# RFID.net
KiCad netlist of a schematic drawn in Altium Designer
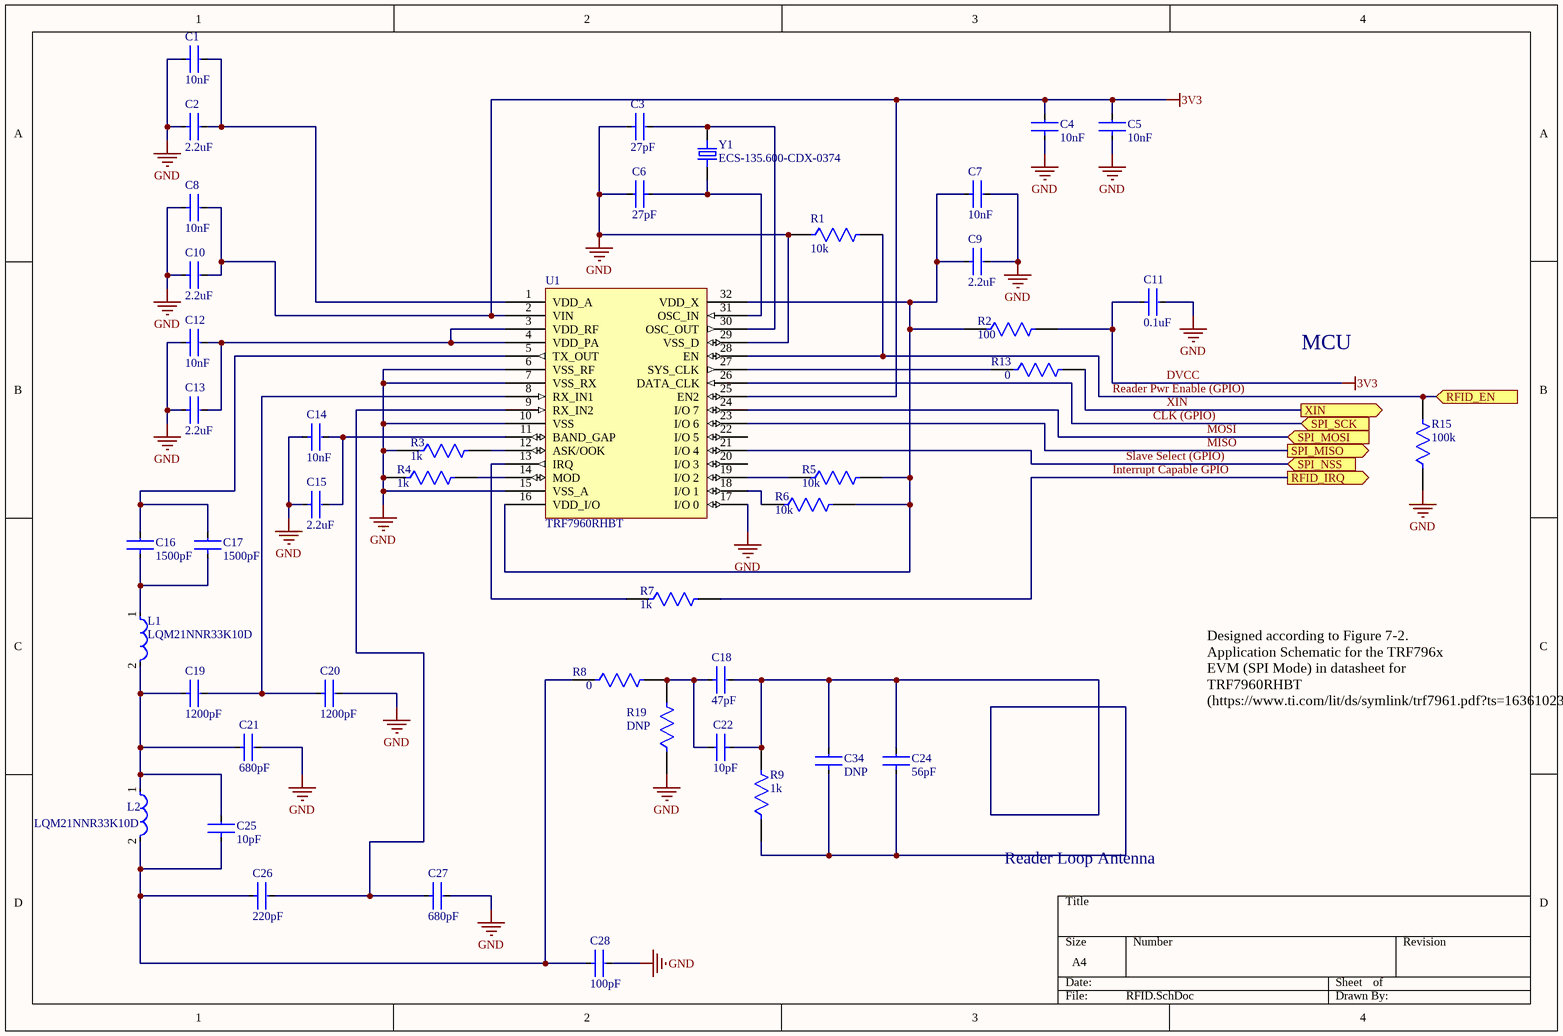
[diagram p0: RFID.SchDoc]

(export (version "E")
  (design (tool "Eeschema 10.0.6"))
  (components
    (comp (ref "C1")
      (value "10nF")
      (footprint "FP-GCJ21B-0_3-IPC_A")
      (description "Multilayer Ceramic Capacitors MLCC - SMD/SMT 0805 2.2uF 10%, 16VDC,  X7R 15%")
      (fields (field (name "TOLERANCE") "10%"))
      (libsource (lib "Altium Content Vault") (part "02cd4be3c70576c341d710602a673aa"))
    )
    (comp (ref "C2")
      (value "2.2uF")
      (footprint "FP-GCJ21B-0_3-IPC_A")
      (description "Multilayer Ceramic Capacitors MLCC - SMD/SMT 0805 2.2uF 10%, 16VDC,  X7R 15%")
      (fields (field (name "TOLERANCE") "10%"))
      (libsource (lib "Altium Content Vault") (part "02cd4be3c70576c341d710602a673aa"))
    )
    (comp (ref "C3")
      (value "27pF")
      (footprint "FP-GCJ21B-0_3-IPC_A")
      (description "Multilayer Ceramic Capacitors MLCC - SMD/SMT 0805 2.2uF 10%, 16VDC,  X7R 15%")
      (fields (field (name "TOLERANCE") "10%"))
      (libsource (lib "Altium Content Vault") (part "02cd4be3c70576c341d710602a673aa"))
    )
    (comp (ref "C4")
      (value "10nF")
      (footprint "FP-GCJ21B-0_3-IPC_A")
      (description "Multilayer Ceramic Capacitors MLCC - SMD/SMT 0805 2.2uF 10%, 16VDC,  X7R 15%")
      (fields (field (name "TOLERANCE") "10%"))
      (libsource (lib "Altium Content Vault") (part "02cd4be3c70576c341d710602a673aa"))
    )
    (comp (ref "C5")
      (value "10nF")
      (footprint "FP-GCJ21B-0_3-IPC_A")
      (description "Multilayer Ceramic Capacitors MLCC - SMD/SMT 0805 2.2uF 10%, 16VDC,  X7R 15%")
      (fields (field (name "TOLERANCE") "10%"))
      (libsource (lib "Altium Content Vault") (part "02cd4be3c70576c341d710602a673aa"))
    )
    (comp (ref "C6")
      (value "27pF")
      (footprint "FP-GCJ21B-0_3-IPC_A")
      (description "Multilayer Ceramic Capacitors MLCC - SMD/SMT 0805 2.2uF 10%, 16VDC,  X7R 15%")
      (fields (field (name "TOLERANCE") "10%"))
      (libsource (lib "Altium Content Vault") (part "02cd4be3c70576c341d710602a673aa"))
    )
    (comp (ref "C7")
      (value "10nF")
      (footprint "FP-GCJ21B-0_3-IPC_A")
      (description "Multilayer Ceramic Capacitors MLCC - SMD/SMT 0805 2.2uF 10%, 16VDC,  X7R 15%")
      (fields (field (name "TOLERANCE") "10%"))
      (libsource (lib "Altium Content Vault") (part "02cd4be3c70576c341d710602a673aa"))
    )
    (comp (ref "C8")
      (value "10nF")
      (footprint "FP-GCJ21B-0_3-IPC_A")
      (description "Multilayer Ceramic Capacitors MLCC - SMD/SMT 0805 2.2uF 10%, 16VDC,  X7R 15%")
      (fields (field (name "TOLERANCE") "10%"))
      (libsource (lib "Altium Content Vault") (part "02cd4be3c70576c341d710602a673aa"))
    )
    (comp (ref "C9")
      (value "2.2uF")
      (footprint "FP-GCJ21B-0_3-IPC_A")
      (description "Multilayer Ceramic Capacitors MLCC - SMD/SMT 0805 2.2uF 10%, 16VDC,  X7R 15%")
      (fields (field (name "TOLERANCE") "10%"))
      (libsource (lib "Altium Content Vault") (part "02cd4be3c70576c341d710602a673aa"))
    )
    (comp (ref "C10")
      (value "2.2uF")
      (footprint "FP-GCJ21B-0_3-IPC_A")
      (description "Multilayer Ceramic Capacitors MLCC - SMD/SMT 0805 2.2uF 10%, 16VDC,  X7R 15%")
      (fields (field (name "TOLERANCE") "10%"))
      (libsource (lib "Altium Content Vault") (part "02cd4be3c70576c341d710602a673aa"))
    )
    (comp (ref "C11")
      (value "0.1uF")
      (footprint "FP-GCJ21B-0_3-IPC_A")
      (description "Multilayer Ceramic Capacitors MLCC - SMD/SMT 0805 2.2uF 10%, 16VDC,  X7R 15%")
      (fields (field (name "TOLERANCE") "10%"))
      (libsource (lib "Altium Content Vault") (part "02cd4be3c70576c341d710602a673aa"))
    )
    (comp (ref "C12")
      (value "10nF")
      (footprint "FP-GCJ21B-0_3-IPC_A")
      (description "Multilayer Ceramic Capacitors MLCC - SMD/SMT 0805 2.2uF 10%, 16VDC,  X7R 15%")
      (fields (field (name "TOLERANCE") "10%"))
      (libsource (lib "Altium Content Vault") (part "02cd4be3c70576c341d710602a673aa"))
    )
    (comp (ref "C13")
      (value "2.2uF")
      (footprint "FP-GCJ21B-0_3-IPC_A")
      (description "Multilayer Ceramic Capacitors MLCC - SMD/SMT 0805 2.2uF 10%, 16VDC,  X7R 15%")
      (fields (field (name "TOLERANCE") "10%"))
      (libsource (lib "Altium Content Vault") (part "02cd4be3c70576c341d710602a673aa"))
    )
    (comp (ref "C14")
      (value "10nF")
      (footprint "FP-GCJ21B-0_3-IPC_A")
      (description "Multilayer Ceramic Capacitors MLCC - SMD/SMT 0805 2.2uF 10%, 16VDC,  X7R 15%")
      (fields (field (name "TOLERANCE") "10%"))
      (libsource (lib "Altium Content Vault") (part "02cd4be3c70576c341d710602a673aa"))
    )
    (comp (ref "C15")
      (value "2.2uF")
      (footprint "FP-GCJ21B-0_3-IPC_A")
      (description "Multilayer Ceramic Capacitors MLCC - SMD/SMT 0805 2.2uF 10%, 16VDC,  X7R 15%")
      (fields (field (name "TOLERANCE") "10%"))
      (libsource (lib "Altium Content Vault") (part "02cd4be3c70576c341d710602a673aa"))
    )
    (comp (ref "C16")
      (value "1500pF")
      (footprint "FP-GCJ21B-0_3-IPC_A")
      (description "Multilayer Ceramic Capacitors MLCC - SMD/SMT 0805 2.2uF 10%, 16VDC,  X7R 15%")
      (fields (field (name "TOLERANCE") "10%"))
      (libsource (lib "Altium Content Vault") (part "02cd4be3c70576c341d710602a673aa"))
    )
    (comp (ref "C17")
      (value "1500pF")
      (footprint "FP-GCJ21B-0_3-IPC_A")
      (description "Multilayer Ceramic Capacitors MLCC - SMD/SMT 0805 2.2uF 10%, 16VDC,  X7R 15%")
      (fields (field (name "TOLERANCE") "10%"))
      (libsource (lib "Altium Content Vault") (part "02cd4be3c70576c341d710602a673aa"))
    )
    (comp (ref "C18")
      (value "47pF")
      (footprint "FP-GCJ21B-0_3-IPC_A")
      (description "Multilayer Ceramic Capacitors MLCC - SMD/SMT 0805 2.2uF 10%, 16VDC,  X7R 15%")
      (fields (field (name "TOLERANCE") "10%"))
      (libsource (lib "Altium Content Vault") (part "02cd4be3c70576c341d710602a673aa"))
    )
    (comp (ref "C19")
      (value "1200pF")
      (footprint "FP-GCJ21B-0_3-IPC_A")
      (description "Multilayer Ceramic Capacitors MLCC - SMD/SMT 0805 2.2uF 10%, 16VDC,  X7R 15%")
      (fields (field (name "TOLERANCE") "10%"))
      (libsource (lib "Altium Content Vault") (part "02cd4be3c70576c341d710602a673aa"))
    )
    (comp (ref "C20")
      (value "1200pF")
      (footprint "FP-GCJ21B-0_3-IPC_A")
      (description "Multilayer Ceramic Capacitors MLCC - SMD/SMT 0805 2.2uF 10%, 16VDC,  X7R 15%")
      (fields (field (name "TOLERANCE") "10%"))
      (libsource (lib "Altium Content Vault") (part "02cd4be3c70576c341d710602a673aa"))
    )
    (comp (ref "C21")
      (value "680pF")
      (footprint "FP-GCJ21B-0_3-IPC_A")
      (description "Multilayer Ceramic Capacitors MLCC - SMD/SMT 0805 2.2uF 10%, 16VDC,  X7R 15%")
      (fields (field (name "TOLERANCE") "10%"))
      (libsource (lib "Altium Content Vault") (part "02cd4be3c70576c341d710602a673aa"))
    )
    (comp (ref "C22")
      (value "10pF")
      (footprint "FP-GCJ21B-0_3-IPC_A")
      (description "Multilayer Ceramic Capacitors MLCC - SMD/SMT 0805 2.2uF 10%, 16VDC,  X7R 15%")
      (fields (field (name "TOLERANCE") "10%"))
      (libsource (lib "Altium Content Vault") (part "02cd4be3c70576c341d710602a673aa"))
    )
    (comp (ref "C24")
      (value "56pF")
      (footprint "FP-GCJ21B-0_3-IPC_A")
      (description "Multilayer Ceramic Capacitors MLCC - SMD/SMT 0805 2.2uF 10%, 16VDC,  X7R 15%")
      (fields (field (name "TOLERANCE") "10%"))
      (libsource (lib "Altium Content Vault") (part "02cd4be3c70576c341d710602a673aa"))
    )
    (comp (ref "C25")
      (value "10pF")
      (footprint "FP-GCJ21B-0_3-IPC_A")
      (description "Multilayer Ceramic Capacitors MLCC - SMD/SMT 0805 2.2uF 10%, 16VDC,  X7R 15%")
      (fields (field (name "TOLERANCE") "10%"))
      (libsource (lib "Altium Content Vault") (part "02cd4be3c70576c341d710602a673aa"))
    )
    (comp (ref "C26")
      (value "220pF")
      (footprint "FP-GCJ21B-0_3-IPC_A")
      (description "Multilayer Ceramic Capacitors MLCC - SMD/SMT 0805 2.2uF 10%, 16VDC,  X7R 15%")
      (fields (field (name "TOLERANCE") "10%"))
      (libsource (lib "Altium Content Vault") (part "02cd4be3c70576c341d710602a673aa"))
    )
    (comp (ref "C27")
      (value "680pF")
      (footprint "FP-GCJ21B-0_3-IPC_A")
      (description "Multilayer Ceramic Capacitors MLCC - SMD/SMT 0805 2.2uF 10%, 16VDC,  X7R 15%")
      (fields (field (name "TOLERANCE") "10%"))
      (libsource (lib "Altium Content Vault") (part "02cd4be3c70576c341d710602a673aa"))
    )
    (comp (ref "C28")
      (value "100pF")
      (footprint "FP-GCJ21B-0_3-IPC_A")
      (description "Multilayer Ceramic Capacitors MLCC - SMD/SMT 0805 2.2uF 10%, 16VDC,  X7R 15%")
      (fields (field (name "TOLERANCE") "10%"))
      (libsource (lib "Altium Content Vault") (part "02cd4be3c70576c341d710602a673aa"))
    )
    (comp (ref "C34")
      (value "DNP")
      (footprint "FP-GCJ21B-0_3-IPC_A")
      (description "Multilayer Ceramic Capacitors MLCC - SMD/SMT 0805 2.2uF 10%, 16VDC,  X7R 15%")
      (fields (field (name "TOLERANCE") "10%"))
      (libsource (lib "Altium Content Vault") (part "02cd4be3c70576c341d710602a673aa"))
    )
    (comp (ref "L1")
      (value "LQM21NNR33K10D")
      (footprint "FP-LQM21DN_00-IPC_A")
      (description "Multilayer Type Inductor for General Circuits, 0805 (2012), 0.33μH, 10%, 0.48Ω, 250mA")
      (fields (field (name "TOLERANCE") "10%"))
      (libsource (lib "Altium Content Vault") (part "725321dda6339637d4d059423bc1c3c"))
    )
    (comp (ref "L2")
      (value "LQM21NNR33K10D")
      (footprint "FP-LQM21DN_00-IPC_A")
      (description "Multilayer Type Inductor for General Circuits, 0805 (2012), 0.33μH, 10%, 0.48Ω, 250mA")
      (fields (field (name "TOLERANCE") "10%"))
      (libsource (lib "Altium Content Vault") (part "725321dda6339637d4d059423bc1c3c"))
    )
    (comp (ref "R1")
      (value "10k")
      (footprint "FP-AC0603-MFG")
      (description "RES SMD 60.4 OHM 1% 1/10W 0603")
      (fields
        (field (name "MANUFACTURER PART NUMBER") "AC0603FR-0760R4L")
        (field (name "OCTOPART") "https://octopart.com/ac0603fr-0760r4l-yageo-71367350")
      )
      (libsource (lib "Altium Content Vault") (part "1029c3af85768c4190bb7ad29bc67b5"))
    )
    (comp (ref "R2")
      (value "100")
      (footprint "FP-AC0603-MFG")
      (description "RES SMD 60.4 OHM 1% 1/10W 0603")
      (fields
        (field (name "MANUFACTURER PART NUMBER") "AC0603FR-0760R4L")
        (field (name "OCTOPART") "https://octopart.com/ac0603fr-0760r4l-yageo-71367350")
      )
      (libsource (lib "Altium Content Vault") (part "1029c3af85768c4190bb7ad29bc67b5"))
    )
    (comp (ref "R3")
      (value "1k")
      (footprint "FP-AC0603-MFG")
      (description "RES SMD 60.4 OHM 1% 1/10W 0603")
      (fields
        (field (name "MANUFACTURER PART NUMBER") "AC0603FR-0760R4L")
        (field (name "OCTOPART") "https://octopart.com/ac0603fr-0760r4l-yageo-71367350")
      )
      (libsource (lib "Altium Content Vault") (part "1029c3af85768c4190bb7ad29bc67b5"))
    )
    (comp (ref "R4")
      (value "1k")
      (footprint "FP-AC0603-MFG")
      (description "RES SMD 60.4 OHM 1% 1/10W 0603")
      (fields
        (field (name "MANUFACTURER PART NUMBER") "AC0603FR-0760R4L")
        (field (name "OCTOPART") "https://octopart.com/ac0603fr-0760r4l-yageo-71367350")
      )
      (libsource (lib "Altium Content Vault") (part "1029c3af85768c4190bb7ad29bc67b5"))
    )
    (comp (ref "R5")
      (value "10k")
      (footprint "FP-AC0603-MFG")
      (description "RES SMD 60.4 OHM 1% 1/10W 0603")
      (fields
        (field (name "MANUFACTURER PART NUMBER") "AC0603FR-0760R4L")
        (field (name "OCTOPART") "https://octopart.com/ac0603fr-0760r4l-yageo-71367350")
      )
      (libsource (lib "Altium Content Vault") (part "1029c3af85768c4190bb7ad29bc67b5"))
    )
    (comp (ref "R6")
      (value "10k")
      (footprint "FP-AC0603-MFG")
      (description "RES SMD 60.4 OHM 1% 1/10W 0603")
      (fields
        (field (name "MANUFACTURER PART NUMBER") "AC0603FR-0760R4L")
        (field (name "OCTOPART") "https://octopart.com/ac0603fr-0760r4l-yageo-71367350")
      )
      (libsource (lib "Altium Content Vault") (part "1029c3af85768c4190bb7ad29bc67b5"))
    )
    (comp (ref "R7")
      (value "1k")
      (footprint "FP-AC0603-MFG")
      (description "RES SMD 60.4 OHM 1% 1/10W 0603")
      (fields
        (field (name "MANUFACTURER PART NUMBER") "AC0603FR-0760R4L")
        (field (name "OCTOPART") "https://octopart.com/ac0603fr-0760r4l-yageo-71367350")
      )
      (libsource (lib "Altium Content Vault") (part "1029c3af85768c4190bb7ad29bc67b5"))
    )
    (comp (ref "R8")
      (value "0")
      (footprint "FP-AC0603-MFG")
      (description "RES SMD 60.4 OHM 1% 1/10W 0603")
      (fields
        (field (name "MANUFACTURER PART NUMBER") "AC0603FR-0760R4L")
        (field (name "OCTOPART") "https://octopart.com/ac0603fr-0760r4l-yageo-71367350")
      )
      (libsource (lib "Altium Content Vault") (part "1029c3af85768c4190bb7ad29bc67b5"))
    )
    (comp (ref "R9")
      (value "1k")
      (footprint "FP-AC0603-MFG")
      (description "RES SMD 60.4 OHM 1% 1/10W 0603")
      (fields
        (field (name "MANUFACTURER PART NUMBER") "AC0603FR-0760R4L")
        (field (name "OCTOPART") "https://octopart.com/ac0603fr-0760r4l-yageo-71367350")
      )
      (libsource (lib "Altium Content Vault") (part "1029c3af85768c4190bb7ad29bc67b5"))
    )
    (comp (ref "R13")
      (value "0")
      (footprint "FP-AC0603-MFG")
      (description "RES SMD 60.4 OHM 1% 1/10W 0603")
      (fields
        (field (name "MANUFACTURER PART NUMBER") "AC0603FR-0760R4L")
        (field (name "OCTOPART") "https://octopart.com/ac0603fr-0760r4l-yageo-71367350")
      )
      (libsource (lib "Altium Content Vault") (part "1029c3af85768c4190bb7ad29bc67b5"))
    )
    (comp (ref "R15")
      (value "100k")
      (footprint "FP-AC0603-MFG")
      (description "RES SMD 60.4 OHM 1% 1/10W 0603")
      (fields
        (field (name "MANUFACTURER PART NUMBER") "AC0603FR-0760R4L")
        (field (name "OCTOPART") "https://octopart.com/ac0603fr-0760r4l-yageo-71367350")
      )
      (libsource (lib "Altium Content Vault") (part "1029c3af85768c4190bb7ad29bc67b5"))
    )
    (comp (ref "R19")
      (value "DNP")
      (footprint "FP-AC0603-MFG")
      (description "RES SMD 60.4 OHM 1% 1/10W 0603")
      (fields
        (field (name "MANUFACTURER PART NUMBER") "AC0603FR-0760R4L")
        (field (name "OCTOPART") "https://octopart.com/ac0603fr-0760r4l-yageo-71367350")
      )
      (libsource (lib "Altium Content Vault") (part "1029c3af85768c4190bb7ad29bc67b5"))
    )
    (comp (ref "U1")
      (value "TRF7960RHBT")
      (footprint "IC_ADS125H01IRHBT")
      (description "TRF7960 Multi-Protocol Fully Integrated 13.56-MHz RFID Reader/Writer IC 32-VQFN -40 to 110")
      (libsource (lib "Schlib") (part "TRF7960RHBT"))
    )
    (comp (ref "Y1")
      (value "ECS-135.600-CDX-0374")
      (footprint "XTAL_ECS-135.600-CDX-0374")
      (libsource (lib "Schlib") (part "ECS-135.600-CDX-0374"))
    )
  )
  (nets
    (net (code "1") (name "/CLK (GPIO)") (class "Default")
      (node (ref "U1") (pin "26") (pinfunction "DATA_CLK_26") (pintype "input"))
    )
    (net (code "2") (name "/Interrupt Capable GPIO") (class "Default")
      (node (ref "R7") (pin "2") (pinfunction "2_2") (pintype "passive"))
    )
    (net (code "3") (name "/MISO") (class "Default")
      (node (ref "U1") (pin "23") (pinfunction "I/O_6_23") (pintype "bidirectional"))
    )
    (net (code "4") (name "/MOSI") (class "Default")
      (node (ref "U1") (pin "24") (pinfunction "I/O_7_24") (pintype "bidirectional"))
    )
    (net (code "5") (name "/Reader Pwr Enable (GPIO)") (class "Default")
      (node (ref "R1") (pin "2") (pinfunction "2_2") (pintype "passive"))
      (node (ref "R15") (pin "2") (pinfunction "2_2") (pintype "passive"))
      (node (ref "U1") (pin "28") (pinfunction "EN_28") (pintype "bidirectional"))
    )
    (net (code "6") (name "/Slave Select (GPIO)") (class "Default")
      (node (ref "U1") (pin "21") (pinfunction "I/O_4_21") (pintype "bidirectional"))
    )
    (net (code "7") (name "/XIN") (class "Default")
      (node (ref "R13") (pin "2") (pinfunction "2_2") (pintype "passive"))
    )
    (net (code "8") (name "3V3") (class "Default")
      (node (ref "C10") (pin "2") (pinfunction "2_2") (pintype "passive"))
      (node (ref "C11") (pin "1") (pinfunction "1_1") (pintype "passive"))
      (node (ref "C4") (pin "2") (pinfunction "2_2") (pintype "passive"))
      (node (ref "C5") (pin "2") (pinfunction "2_2") (pintype "passive"))
      (node (ref "C8") (pin "2") (pinfunction "2_2") (pintype "passive"))
      (node (ref "R2") (pin "2") (pinfunction "2_2") (pintype "passive"))
      (node (ref "U1") (pin "2") (pinfunction "VIN_2") (pintype "power_in"))
      (node (ref "U1") (pin "25") (pinfunction "EN2_25") (pintype "bidirectional"))
    )
    (net (code "9") (name "GND") (class "Default")
      (node (ref "C1") (pin "1") (pinfunction "1_1") (pintype "passive"))
      (node (ref "C10") (pin "1") (pinfunction "1_1") (pintype "passive"))
      (node (ref "C11") (pin "2") (pinfunction "2_2") (pintype "passive"))
      (node (ref "C12") (pin "1") (pinfunction "1_1") (pintype "passive"))
      (node (ref "C13") (pin "1") (pinfunction "1_1") (pintype "passive"))
      (node (ref "C14") (pin "1") (pinfunction "1_1") (pintype "passive"))
      (node (ref "C15") (pin "1") (pinfunction "1_1") (pintype "passive"))
      (node (ref "C2") (pin "1") (pinfunction "1_1") (pintype "passive"))
      (node (ref "C20") (pin "2") (pinfunction "2_2") (pintype "passive"))
      (node (ref "C21") (pin "2") (pinfunction "2_2") (pintype "passive"))
      (node (ref "C27") (pin "2") (pinfunction "2_2") (pintype "passive"))
      (node (ref "C28") (pin "2") (pinfunction "2_2") (pintype "passive"))
      (node (ref "C3") (pin "1") (pinfunction "1_1") (pintype "passive"))
      (node (ref "C4") (pin "1") (pinfunction "1_1") (pintype "passive"))
      (node (ref "C5") (pin "1") (pinfunction "1_1") (pintype "passive"))
      (node (ref "C6") (pin "2") (pinfunction "2_2") (pintype "passive"))
      (node (ref "C7") (pin "2") (pinfunction "2_2") (pintype "passive"))
      (node (ref "C8") (pin "1") (pinfunction "1_1") (pintype "passive"))
      (node (ref "C9") (pin "2") (pinfunction "2_2") (pintype "passive"))
      (node (ref "R1") (pin "1") (pinfunction "1_1") (pintype "passive"))
      (node (ref "R15") (pin "1") (pinfunction "1_1") (pintype "passive"))
      (node (ref "R19") (pin "1") (pinfunction "1_1") (pintype "passive"))
      (node (ref "R3") (pin "1") (pinfunction "1_1") (pintype "passive"))
      (node (ref "R4") (pin "1") (pinfunction "1_1") (pintype "passive"))
      (node (ref "U1") (pin "10") (pinfunction "VSS_10") (pintype "power_in"))
      (node (ref "U1") (pin "15") (pinfunction "VSS_A_15") (pintype "power_in"))
      (node (ref "U1") (pin "17") (pinfunction "I/O_0_17") (pintype "bidirectional"))
      (node (ref "U1") (pin "29") (pinfunction "VSS_D_29") (pintype "bidirectional"))
      (node (ref "U1") (pin "6") (pinfunction "VSS_RF_6") (pintype "power_in"))
      (node (ref "U1") (pin "7") (pinfunction "VSS_RX_7") (pintype "power_in"))
    )
    (net (code "10") (name "Net-(C16-Pad1)") (class "Default")
      (node (ref "C16") (pin "1") (pinfunction "1_1") (pintype "passive"))
      (node (ref "C17") (pin "1") (pinfunction "1_1") (pintype "passive"))
      (node (ref "L1") (pin "1") (pinfunction "1_1") (pintype "passive"))
    )
    (net (code "11") (name "Net-(C18-Pad1)") (class "Default")
      (node (ref "C18") (pin "1") (pinfunction "1_1") (pintype "passive"))
      (node (ref "C22") (pin "2") (pinfunction "2_2") (pintype "passive"))
      (node (ref "R19") (pin "2") (pinfunction "2_2") (pintype "passive"))
      (node (ref "R8") (pin "2") (pinfunction "2_2") (pintype "passive"))
    )
    (net (code "12") (name "Net-(C18-Pad2)") (class "Default")
      (node (ref "C18") (pin "2") (pinfunction "2_2") (pintype "passive"))
      (node (ref "C22") (pin "1") (pinfunction "1_1") (pintype "passive"))
      (node (ref "C24") (pin "1") (pinfunction "1_1") (pintype "passive"))
      (node (ref "C24") (pin "2") (pinfunction "2_2") (pintype "passive"))
      (node (ref "C34") (pin "1") (pinfunction "1_1") (pintype "passive"))
      (node (ref "C34") (pin "2") (pinfunction "2_2") (pintype "passive"))
      (node (ref "R9") (pin "1") (pinfunction "1_1") (pintype "passive"))
      (node (ref "R9") (pin "2") (pinfunction "2_2") (pintype "passive"))
    )
    (net (code "13") (name "Net-(C19-Pad1)") (class "Default")
      (node (ref "C19") (pin "1") (pinfunction "1_1") (pintype "passive"))
      (node (ref "C21") (pin "1") (pinfunction "1_1") (pintype "passive"))
      (node (ref "C25") (pin "2") (pinfunction "2_2") (pintype "passive"))
      (node (ref "L1") (pin "2") (pinfunction "2_2") (pintype "passive"))
      (node (ref "L2") (pin "1") (pinfunction "1_1") (pintype "passive"))
    )
    (net (code "14") (name "Net-(C25-Pad1)") (class "Default")
      (node (ref "C25") (pin "1") (pinfunction "1_1") (pintype "passive"))
      (node (ref "C26") (pin "1") (pinfunction "1_1") (pintype "passive"))
      (node (ref "C28") (pin "1") (pinfunction "1_1") (pintype "passive"))
      (node (ref "L2") (pin "2") (pinfunction "2_2") (pintype "passive"))
      (node (ref "R8") (pin "1") (pinfunction "1_1") (pintype "passive"))
    )
    (net (code "15") (name "Net-(U1-ASK{slash}OOK)") (class "Default")
      (node (ref "R3") (pin "2") (pinfunction "2_2") (pintype "passive"))
      (node (ref "U1") (pin "12") (pinfunction "ASK/OOK_12") (pintype "bidirectional"))
    )
    (net (code "16") (name "Net-(U1-BAND_GAP)") (class "Default")
      (node (ref "C14") (pin "2") (pinfunction "2_2") (pintype "passive"))
      (node (ref "C15") (pin "2") (pinfunction "2_2") (pintype "passive"))
      (node (ref "U1") (pin "11") (pinfunction "BAND_GAP_11") (pintype "bidirectional"))
    )
    (net (code "17") (name "Net-(U1-IRQ)") (class "Default")
      (node (ref "R7") (pin "1") (pinfunction "1_1") (pintype "passive"))
      (node (ref "U1") (pin "13") (pinfunction "IRQ_13") (pintype "output"))
    )
    (net (code "18") (name "Net-(U1-I{slash}O_1)") (class "Default")
      (node (ref "R6") (pin "1") (pinfunction "1_1") (pintype "passive"))
      (node (ref "U1") (pin "18") (pinfunction "I/O_1_18") (pintype "bidirectional"))
    )
    (net (code "19") (name "Net-(U1-I{slash}O_2)") (class "Default")
      (node (ref "R5") (pin "1") (pinfunction "1_1") (pintype "passive"))
      (node (ref "U1") (pin "19") (pinfunction "I/O_2_19") (pintype "bidirectional"))
    )
    (net (code "20") (name "Net-(U1-MOD)") (class "Default")
      (node (ref "R4") (pin "2") (pinfunction "2_2") (pintype "passive"))
      (node (ref "U1") (pin "14") (pinfunction "MOD_14") (pintype "bidirectional"))
    )
    (net (code "21") (name "Net-(U1-OSC_IN)") (class "Default")
      (node (ref "C6") (pin "1") (pinfunction "1_1") (pintype "passive"))
      (node (ref "U1") (pin "31") (pinfunction "OSC_IN_31") (pintype "input"))
      (node (ref "Y1") (pin "1") (pinfunction "1_1") (pintype "passive"))
    )
    (net (code "22") (name "Net-(U1-OSC_OUT)") (class "Default")
      (node (ref "C3") (pin "2") (pinfunction "2_2") (pintype "passive"))
      (node (ref "U1") (pin "30") (pinfunction "OSC_OUT_30") (pintype "output"))
      (node (ref "Y1") (pin "2") (pinfunction "2_2") (pintype "passive"))
    )
    (net (code "23") (name "Net-(U1-RX_IN1)") (class "Default")
      (node (ref "C19") (pin "2") (pinfunction "2_2") (pintype "passive"))
      (node (ref "C20") (pin "1") (pinfunction "1_1") (pintype "passive"))
      (node (ref "U1") (pin "8") (pinfunction "RX_IN1_8") (pintype "input"))
    )
    (net (code "24") (name "Net-(U1-RX_IN2)") (class "Default")
      (node (ref "C26") (pin "2") (pinfunction "2_2") (pintype "passive"))
      (node (ref "C27") (pin "1") (pinfunction "1_1") (pintype "passive"))
      (node (ref "U1") (pin "9") (pinfunction "RX_IN2_9") (pintype "input"))
    )
    (net (code "25") (name "Net-(U1-SYS_CLK)") (class "Default")
      (node (ref "R13") (pin "1") (pinfunction "1_1") (pintype "passive"))
      (node (ref "U1") (pin "27") (pinfunction "SYS_CLK_27") (pintype "output"))
    )
    (net (code "26") (name "Net-(U1-TX_OUT)") (class "Default")
      (node (ref "C16") (pin "2") (pinfunction "2_2") (pintype "passive"))
      (node (ref "C17") (pin "2") (pinfunction "2_2") (pintype "passive"))
      (node (ref "U1") (pin "5") (pinfunction "TX_OUT_5") (pintype "output"))
    )
    (net (code "27") (name "Net-(U1-VDD_A)") (class "Default")
      (node (ref "C1") (pin "2") (pinfunction "2_2") (pintype "passive"))
      (node (ref "C2") (pin "2") (pinfunction "2_2") (pintype "passive"))
      (node (ref "U1") (pin "1") (pinfunction "VDD_A_1") (pintype "power_in"))
    )
    (net (code "28") (name "Net-(U1-VDD_I{slash}O)") (class "Default")
      (node (ref "C7") (pin "1") (pinfunction "1_1") (pintype "passive"))
      (node (ref "C9") (pin "1") (pinfunction "1_1") (pintype "passive"))
      (node (ref "R2") (pin "1") (pinfunction "1_1") (pintype "passive"))
      (node (ref "R5") (pin "2") (pinfunction "2_2") (pintype "passive"))
      (node (ref "R6") (pin "2") (pinfunction "2_2") (pintype "passive"))
      (node (ref "U1") (pin "16") (pinfunction "VDD_I/O_16") (pintype "power_in"))
      (node (ref "U1") (pin "32") (pinfunction "VDD_X_32") (pintype "power_in"))
    )
    (net (code "29") (name "Net-(U1-VDD_PA)") (class "Default")
      (node (ref "C12") (pin "2") (pinfunction "2_2") (pintype "passive"))
      (node (ref "C13") (pin "2") (pinfunction "2_2") (pintype "passive"))
      (node (ref "U1") (pin "3") (pinfunction "VDD_RF_3") (pintype "power_in"))
      (node (ref "U1") (pin "4") (pinfunction "VDD_PA_4") (pintype "power_in"))
    )
    (net (code "30") (name "unconnected-(U1-I{slash}O_3-Pad20)") (class "Default")
      (node (ref "U1") (pin "20") (pinfunction "I/O_3_20") (pintype "bidirectional"))
    )
    (net (code "31") (name "unconnected-(U1-I{slash}O_5-Pad22)") (class "Default")
      (node (ref "U1") (pin "22") (pinfunction "I/O_5_22") (pintype "bidirectional"))
    )
  )
)
